# board1_attiny84.net
KiCad netlist of a schematic drawn in EAGLE
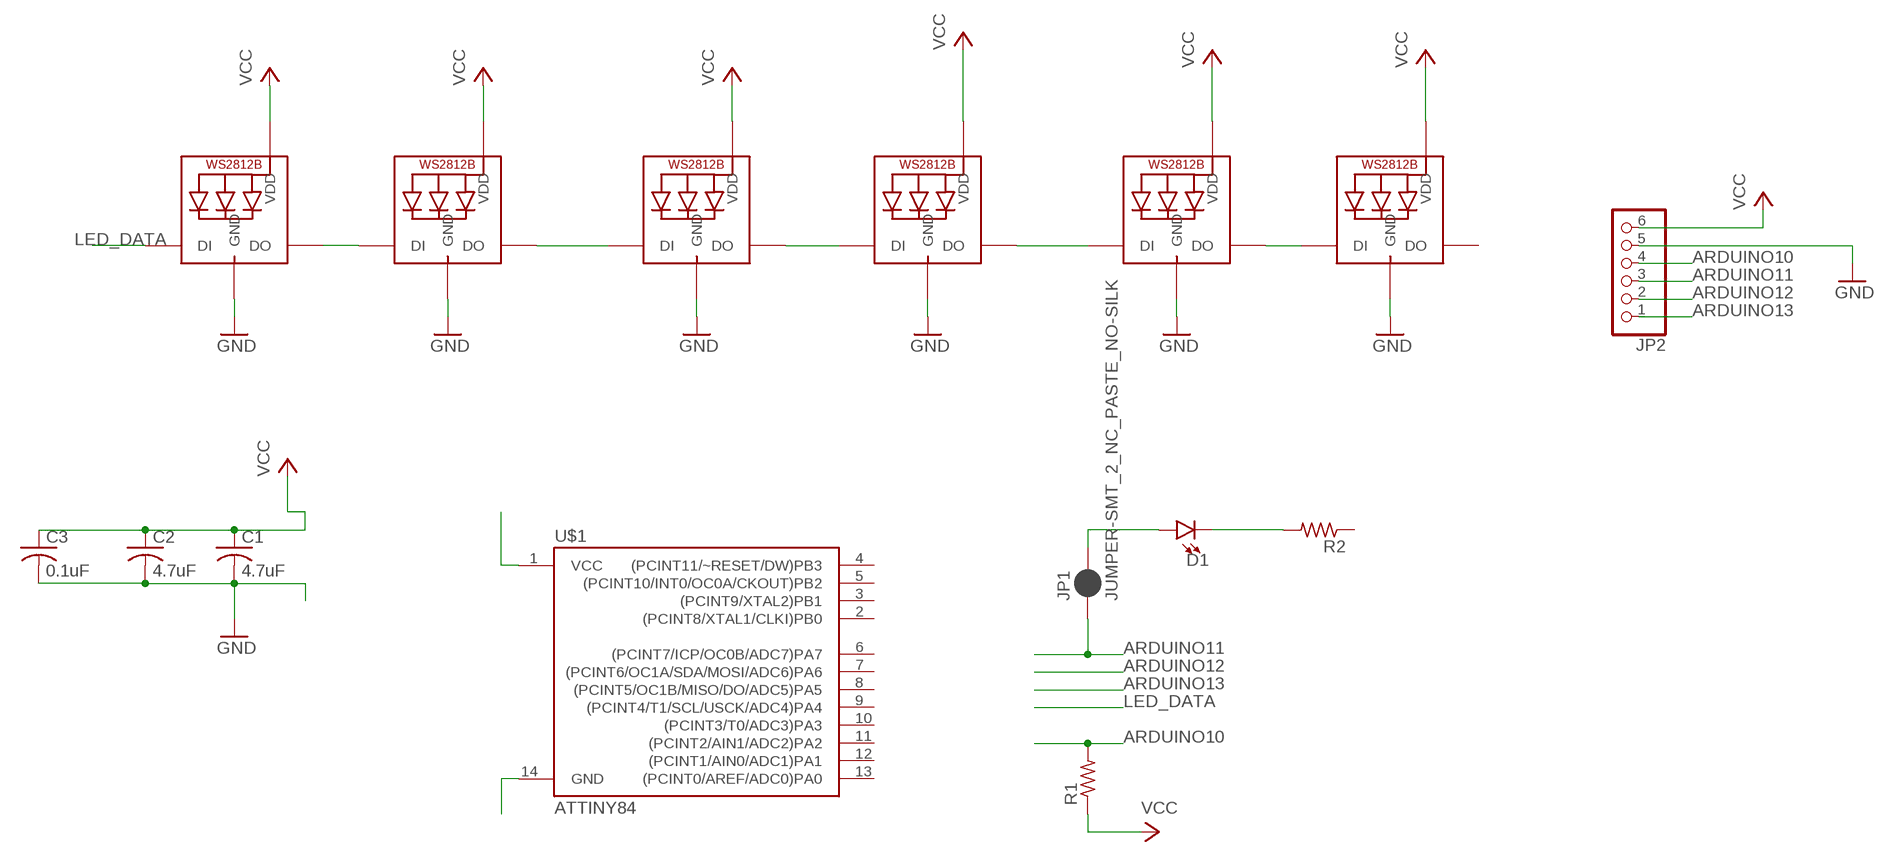
[diagram p0: schematic, sheet 1]

(export (version "E")
  (design (tool "Eeschema 10.0.6"))
  (components
    (comp (ref "C1")
      (value "4.7uF")
      (footprint "eagle-import:C0603")
      (libsource (lib "eagle-import") (part "C-USC0603"))
    )
    (comp (ref "C2")
      (value "4.7uF")
      (footprint "eagle-import:C0603")
      (libsource (lib "eagle-import") (part "C-USC0603"))
    )
    (comp (ref "C3")
      (value "0.1uF")
      (footprint "eagle-import:C0603")
      (libsource (lib "eagle-import") (part "C-USC0603"))
    )
    (comp (ref "D1")
      (value "LED0603")
      (footprint "eagle-import:LED-0603")
      (libsource (lib "eagle-import") (part "LED0603"))
    )
    (comp (ref "JP1")
      (value "JUMPER-SMT_2_NC_PASTE_NO-SILK")
      (footprint "eagle-import:SMT-JUMPER_2_NC_PASTE_NO-SILK")
      (libsource (lib "eagle-import") (part "JUMPER-SMT_2_NC_PASTE_NO-SILK"))
    )
    (comp (ref "JP2")
      (value "PINHD-1X6")
      (footprint "eagle-import:1X06")
      (libsource (lib "eagle-import") (part "PINHD-1X6"))
    )
    (comp (ref "LED1")
      (value "WS2812B5050")
      (footprint "eagle-import:WS2812B")
      (libsource (lib "eagle-import") (part "WS2812B5050"))
    )
    (comp (ref "LED2")
      (value "WS2812B5050")
      (footprint "eagle-import:WS2812B")
      (libsource (lib "eagle-import") (part "WS2812B5050"))
    )
    (comp (ref "LED3")
      (value "WS2812B5050")
      (footprint "eagle-import:WS2812B")
      (libsource (lib "eagle-import") (part "WS2812B5050"))
    )
    (comp (ref "LED4")
      (value "WS2812B5050")
      (footprint "eagle-import:WS2812B")
      (libsource (lib "eagle-import") (part "WS2812B5050"))
    )
    (comp (ref "LED5")
      (value "WS2812B5050")
      (footprint "eagle-import:WS2812B")
      (libsource (lib "eagle-import") (part "WS2812B5050"))
    )
    (comp (ref "LED6")
      (value "WS2812B5050")
      (footprint "eagle-import:WS2812B")
      (libsource (lib "eagle-import") (part "WS2812B5050"))
    )
    (comp (ref "R1")
      (value "R-US_R0603")
      (footprint "eagle-import:R0603")
      (libsource (lib "eagle-import") (part "R-US_R0603"))
    )
    (comp (ref "R2")
      (value "R-US_R0603")
      (footprint "eagle-import:R0603")
      (libsource (lib "eagle-import") (part "R-US_R0603"))
    )
    (comp (ref "U$1")
      (value "ATTINY84")
      (footprint "eagle-import:SO14")
      (libsource (lib "eagle-import") (part "ATTINY84"))
    )
  )
  (nets
    (net (code "1") (name "/ARDUINO10") (class "Default")
      (node (ref "JP2") (pin "4") (pinfunction "4_4") (pintype "passive"))
      (node (ref "R1") (pin "2") (pinfunction "2_2") (pintype "passive"))
    )
    (net (code "2") (name "/ARDUINO11") (class "Default")
      (node (ref "JP1") (pin "1") (pinfunction "1_1") (pintype "passive"))
      (node (ref "JP2") (pin "3") (pinfunction "3_3") (pintype "passive"))
    )
    (net (code "3") (name "/ARDUINO12") (class "Default")
      (node (ref "JP2") (pin "2") (pinfunction "2_2") (pintype "passive"))
    )
    (net (code "4") (name "/ARDUINO13") (class "Default")
      (node (ref "JP2") (pin "1") (pinfunction "1_1") (pintype "passive"))
    )
    (net (code "5") (name "/LED_DATA") (class "Default")
      (node (ref "LED1") (pin "4-DIN") (pinfunction "DI_4-DIN") (pintype "input"))
    )
    (net (code "6") (name "GND") (class "Default")
      (node (ref "C1") (pin "2") (pinfunction "2_2") (pintype "passive"))
      (node (ref "C2") (pin "2") (pinfunction "2_2") (pintype "passive"))
      (node (ref "C3") (pin "2") (pinfunction "2_2") (pintype "passive"))
      (node (ref "JP2") (pin "5") (pinfunction "5_5") (pintype "passive"))
      (node (ref "LED1") (pin "3-GND") (pinfunction "GND_3-GND") (pintype "power_in"))
      (node (ref "LED2") (pin "3-GND") (pinfunction "GND_3-GND") (pintype "power_in"))
      (node (ref "LED3") (pin "3-GND") (pinfunction "GND_3-GND") (pintype "power_in"))
      (node (ref "LED4") (pin "3-GND") (pinfunction "GND_3-GND") (pintype "power_in"))
      (node (ref "LED5") (pin "3-GND") (pinfunction "GND_3-GND") (pintype "power_in"))
      (node (ref "LED6") (pin "3-GND") (pinfunction "GND_3-GND") (pintype "power_in"))
    )
    (net (code "7") (name "Net-(D1-PadA)") (class "Default")
      (node (ref "D1") (pin "A") (pinfunction "A_A") (pintype "passive"))
      (node (ref "JP1") (pin "2") (pinfunction "2_2") (pintype "passive"))
    )
    (net (code "8") (name "Net-(D1-PadC)") (class "Default")
      (node (ref "D1") (pin "C") (pinfunction "C_C") (pintype "passive"))
      (node (ref "R2") (pin "2") (pinfunction "2_2") (pintype "passive"))
    )
    (net (code "9") (name "Net-(LED1-DO)") (class "Default")
      (node (ref "LED1") (pin "2-DOUT") (pinfunction "DO_2-DOUT") (pintype "output"))
      (node (ref "LED2") (pin "4-DIN") (pinfunction "DI_4-DIN") (pintype "input"))
    )
    (net (code "10") (name "Net-(LED2-DO)") (class "Default")
      (node (ref "LED2") (pin "2-DOUT") (pinfunction "DO_2-DOUT") (pintype "output"))
      (node (ref "LED3") (pin "4-DIN") (pinfunction "DI_4-DIN") (pintype "input"))
    )
    (net (code "11") (name "Net-(LED3-DO)") (class "Default")
      (node (ref "LED3") (pin "2-DOUT") (pinfunction "DO_2-DOUT") (pintype "output"))
      (node (ref "LED4") (pin "4-DIN") (pinfunction "DI_4-DIN") (pintype "input"))
    )
    (net (code "12") (name "Net-(LED4-DO)") (class "Default")
      (node (ref "LED4") (pin "2-DOUT") (pinfunction "DO_2-DOUT") (pintype "output"))
      (node (ref "LED5") (pin "4-DIN") (pinfunction "DI_4-DIN") (pintype "input"))
    )
    (net (code "13") (name "Net-(LED5-DO)") (class "Default")
      (node (ref "LED5") (pin "2-DOUT") (pinfunction "DO_2-DOUT") (pintype "output"))
      (node (ref "LED6") (pin "4-DIN") (pinfunction "DI_4-DIN") (pintype "input"))
    )
    (net (code "14") (name "VCC") (class "Default")
      (node (ref "C1") (pin "1") (pinfunction "1_1") (pintype "passive"))
      (node (ref "C2") (pin "1") (pinfunction "1_1") (pintype "passive"))
      (node (ref "C3") (pin "1") (pinfunction "1_1") (pintype "passive"))
      (node (ref "JP2") (pin "6") (pinfunction "6_6") (pintype "passive"))
      (node (ref "LED1") (pin "1-VDD") (pinfunction "VDD_1-VDD") (pintype "power_in"))
      (node (ref "LED2") (pin "1-VDD") (pinfunction "VDD_1-VDD") (pintype "power_in"))
      (node (ref "LED3") (pin "1-VDD") (pinfunction "VDD_1-VDD") (pintype "power_in"))
      (node (ref "LED4") (pin "1-VDD") (pinfunction "VDD_1-VDD") (pintype "power_in"))
      (node (ref "LED5") (pin "1-VDD") (pinfunction "VDD_1-VDD") (pintype "power_in"))
      (node (ref "LED6") (pin "1-VDD") (pinfunction "VDD_1-VDD") (pintype "power_in"))
      (node (ref "R1") (pin "1") (pinfunction "1_1") (pintype "passive"))
    )
    (net (code "15") (name "unconnected-(LED6-DO-Pad2-DOUT)") (class "Default")
      (node (ref "LED6") (pin "2-DOUT") (pinfunction "DO_2-DOUT") (pintype "output"))
    )
    (net (code "16") (name "unconnected-(R2-Pad1)") (class "Default")
      (node (ref "R2") (pin "1") (pinfunction "1_1") (pintype "passive"))
    )
    (net (code "17") (name "unconnected-(U$1-(PCINT0{slash}AREF{slash}ADC0)PA0-Pad13)") (class "Default")
      (node (ref "U$1") (pin "13") (pinfunction "(PCINT0/AREF/ADC0)PA0_13") (pintype "bidirectional"))
    )
    (net (code "18") (name "unconnected-(U$1-(PCINT1{slash}AIN0{slash}ADC1)PA1-Pad12)") (class "Default")
      (node (ref "U$1") (pin "12") (pinfunction "(PCINT1/AIN0/ADC1)PA1_12") (pintype "bidirectional"))
    )
    (net (code "19") (name "unconnected-(U$1-(PCINT2{slash}AIN1{slash}ADC2)PA2-Pad11)") (class "Default")
      (node (ref "U$1") (pin "11") (pinfunction "(PCINT2/AIN1/ADC2)PA2_11") (pintype "bidirectional"))
    )
    (net (code "20") (name "unconnected-(U$1-(PCINT3{slash}T0{slash}ADC3)PA3-Pad10)") (class "Default")
      (node (ref "U$1") (pin "10") (pinfunction "(PCINT3/T0/ADC3)PA3_10") (pintype "bidirectional"))
    )
    (net (code "21") (name "unconnected-(U$1-(PCINT4{slash}T1{slash}SCL{slash}USCK{slash}ADC4)PA4-Pad9)") (class "Default")
      (node (ref "U$1") (pin "9") (pinfunction "(PCINT4/T1/SCL/USCK/ADC4)PA4_9") (pintype "bidirectional"))
    )
    (net (code "22") (name "unconnected-(U$1-(PCINT5{slash}OC1B{slash}MISO{slash}DO{slash}ADC5)PA5-Pad8)") (class "Default")
      (node (ref "U$1") (pin "8") (pinfunction "(PCINT5/OC1B/MISO/DO/ADC5)PA5_8") (pintype "bidirectional"))
    )
    (net (code "23") (name "unconnected-(U$1-(PCINT6{slash}OC1A{slash}SDA{slash}MOSI{slash}ADC6)PA6-Pad7)") (class "Default")
      (node (ref "U$1") (pin "7") (pinfunction "(PCINT6/OC1A/SDA/MOSI/ADC6)PA6_7") (pintype "bidirectional"))
    )
    (net (code "24") (name "unconnected-(U$1-(PCINT7{slash}ICP{slash}OC0B{slash}ADC7)PA7-Pad6)") (class "Default")
      (node (ref "U$1") (pin "6") (pinfunction "(PCINT7/ICP/OC0B/ADC7)PA7_6") (pintype "bidirectional"))
    )
    (net (code "25") (name "unconnected-(U$1-(PCINT8{slash}XTAL1{slash}CLKI)PB0-Pad2)") (class "Default")
      (node (ref "U$1") (pin "2") (pinfunction "(PCINT8/XTAL1/CLKI)PB0_2") (pintype "bidirectional"))
    )
    (net (code "26") (name "unconnected-(U$1-(PCINT9{slash}XTAL2)PB1-Pad3)") (class "Default")
      (node (ref "U$1") (pin "3") (pinfunction "(PCINT9/XTAL2)PB1_3") (pintype "bidirectional"))
    )
    (net (code "27") (name "unconnected-(U$1-(PCINT10{slash}INT0{slash}OC0A{slash}CKOUT)PB2-Pad5)") (class "Default")
      (node (ref "U$1") (pin "5") (pinfunction "(PCINT10/INT0/OC0A/CKOUT)PB2_5") (pintype "bidirectional"))
    )
    (net (code "28") (name "unconnected-(U$1-(PCINT11{slash}~{RESET{slash}DW})PB3-Pad4)") (class "Default")
      (node (ref "U$1") (pin "4") (pinfunction "(PCINT11/~{RESET/DW})PB3_4") (pintype "bidirectional"))
    )
    (net (code "29") (name "unconnected-(U$1-GND-Pad14)") (class "Default")
      (node (ref "U$1") (pin "14") (pinfunction "GND_14") (pintype "bidirectional"))
    )
    (net (code "30") (name "unconnected-(U$1-VCC-Pad1)") (class "Default")
      (node (ref "U$1") (pin "1") (pinfunction "VCC_1") (pintype "bidirectional"))
    )
  )
)
